# 1_P1.net
KiCad netlist of a schematic drawn in Altium Designer
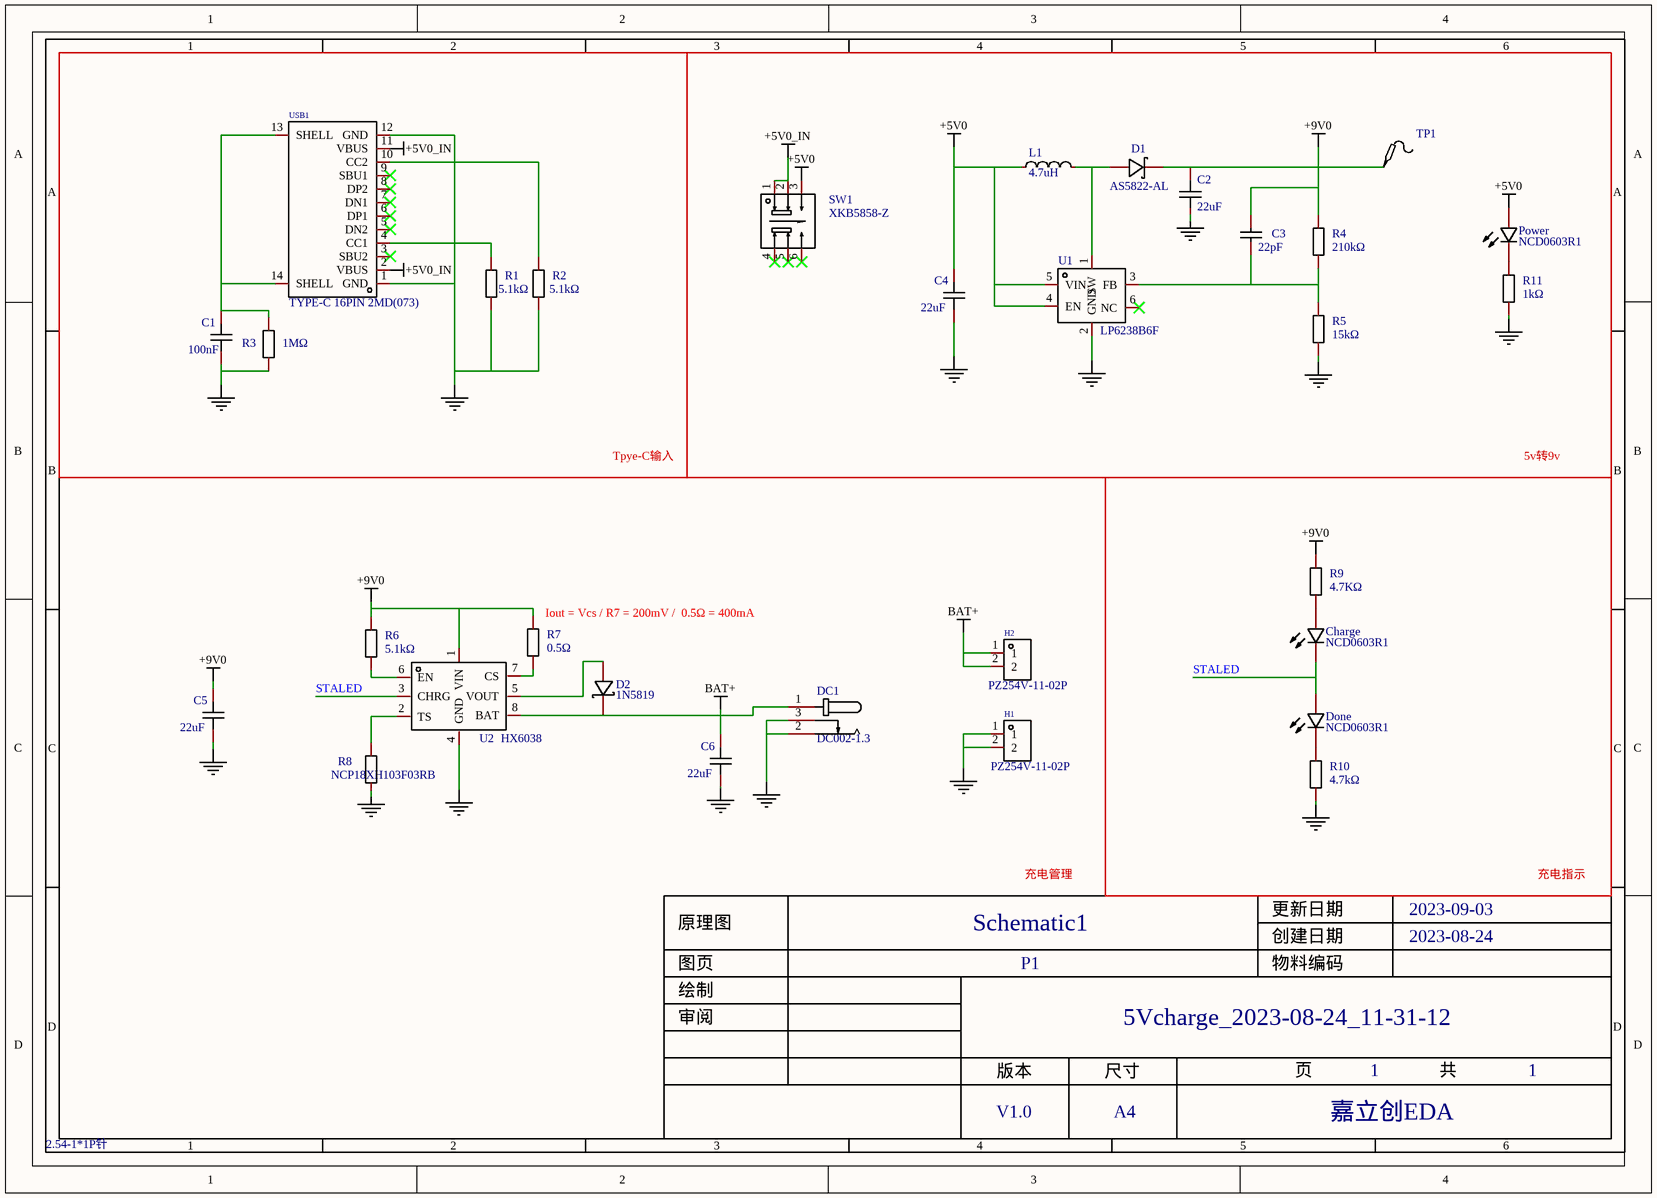
[diagram p0: 1_P1.schdoc]

(export (version "E")
  (design (tool "Eeschema 10.0.6"))
  (components
    (comp (ref "C1")
      (value "100nF")
      (description "容值:100nF;精度:±10%;额定电压:50V;材质(温度系数):X7R;")
      (fields
        (field (name "NAME") "100nF")
        (field (name "MANUFACTURER") "YAGEO(国巨)")
        (field (name "MANUFACTURER PART") "CC0603KRX7R9BB104")
      )
      (libsource (lib "altium-import") (part "root_1_CC0603KRX7R9BB104_"))
    )
    (comp (ref "C2")
      (value "22uF")
      (description "容值:22uF;精度:±10%;额定电压:25V;材质(温度系数):X5R;")
      (fields
        (field (name "NAME") "22uF")
        (field (name "MANUFACTURER") "SAMSUNG(三星)")
        (field (name "MANUFACTURER PART") "CL31A226KAHNNNE")
      )
      (libsource (lib "altium-import") (part "root_1_CL31A226KAHNNNE_"))
    )
    (comp (ref "C3")
      (value "22pF")
      (description "容值:22pF;精度:±5%;额定电压:50V;材质(温度系数):NP0;")
      (fields
        (field (name "NAME") "22pF")
        (field (name "MANUFACTURER") "YAGEO(国巨)")
        (field (name "MANUFACTURER PART") "CC0603JRNPO9BN220")
      )
      (libsource (lib "altium-import") (part "root_1_CC0603JRNPO9BN220_"))
    )
    (comp (ref "C4")
      (value "22uF")
      (description "容值:22uF;精度:±10%;额定电压:25V;材质(温度系数):X5R;")
      (fields
        (field (name "NAME") "22uF")
        (field (name "MANUFACTURER") "SAMSUNG(三星)")
        (field (name "MANUFACTURER PART") "CL31A226KAHNNNE")
      )
      (libsource (lib "altium-import") (part "root_1_CL31A226KAHNNNE_"))
    )
    (comp (ref "C5")
      (value "22uF")
      (description "容值:22uF;精度:±10%;额定电压:25V;材质(温度系数):X5R;")
      (fields
        (field (name "NAME") "22uF")
        (field (name "MANUFACTURER") "SAMSUNG(三星)")
        (field (name "MANUFACTURER PART") "CL31A226KAHNNNE")
      )
      (libsource (lib "altium-import") (part "root_1_CL31A226KAHNNNE_"))
    )
    (comp (ref "C6")
      (value "22uF")
      (description "容值:22uF;精度:±10%;额定电压:25V;材质(温度系数):X5R;")
      (fields
        (field (name "NAME") "22uF")
        (field (name "MANUFACTURER") "SAMSUNG(三星)")
        (field (name "MANUFACTURER PART") "CL31A226KAHNNNE")
      )
      (libsource (lib "altium-import") (part "root_1_CL31A226KAHNNNE_"))
    )
    (comp (ref "Charge")
      (value "NCD0603R1")
      (description "发光颜色:红灯;")
      (fields (field (name "NAME") "NCD0603R1") (field (name "MANUFACTURER") "国星光电"))
      (libsource (lib "altium-import") (part "root_1_NCD0603R1_C84263_"))
    )
    (comp (ref "D1")
      (value "AS5822-AL")
      (description "二极管配置:独立式;直流反向耐压(Vr):40V;平均整流电流(Io):3A;正向压降(Vf):500mV@3A;反向电流(Ir):500uA@40V;")
      (fields (field (name "NAME") "AS5822-AL") (field (name "MANUFACTURER") "AnBon(安邦)"))
      (libsource (lib "altium-import") (part "root_2_AS5822-AL_"))
    )
    (comp (ref "D2")
      (value "1N5819")
      (description "直流反向耐压(Vr):40V;平均整流电流(Io):1A;正向压降(Vf):500mV@1A;")
      (fields (field (name "NAME") "1N5819") (field (name "MANUFACTURER") "KEXIN(科信)"))
      (libsource (lib "altium-import") (part "root_1_1N5819_C437199_"))
    )
    (comp (ref "DC1")
      (value "DC002-1.3")
      (description "连接器类型:DC电源插座;安装方式:弯插;触点内径:2mm;触点外径:6.3mm;额定电流:500mA;额定电压:30V;工作温度范围:-40℃~+55℃;")
      (fields (field (name "NAME") "DC002-1.3") (field (name "MANUFACTURER") "SHOU HAN(首韩)"))
      (libsource (lib "altium-import") (part "root_0_mirrored_DC002-1.3_"))
    )
    (comp (ref "Done")
      (value "NCD0603R1")
      (description "发光颜色:红灯;")
      (fields (field (name "NAME") "NCD0603R1") (field (name "MANUFACTURER") "国星光电"))
      (libsource (lib "altium-import") (part "root_1_NCD0603R1_C84263_"))
    )
    (comp (ref "H1")
      (value "PZ254V-11-02P")
      (fields (field (name "NAME") "PZ254V-11-02P") (field (name "MANUFACTURER") "XFCN(兴飞)"))
      (libsource (lib "altium-import") (part "root_0_PZ254V-11-02P_"))
    )
    (comp (ref "H2")
      (value "PZ254V-11-02P")
      (fields (field (name "NAME") "PZ254V-11-02P") (field (name "MANUFACTURER") "XFCN(兴飞)"))
      (libsource (lib "altium-import") (part "root_0_PZ254V-11-02P_"))
    )
    (comp (ref "L1")
      (value "4.7uH")
      (description "直流电阻(DCR):78mΩ;精度:±20%;电感值:4.7uH;额定电流:2A;")
      (fields
        (field (name "NAME") "4.7uH")
        (field (name "MANUFACTURER") "Sunlord(顺络)")
        (field (name "MANUFACTURER PART") "SWPA4030S4R7MT")
      )
      (libsource (lib "altium-import") (part "root_0_SWPA4030S4R7MT_"))
    )
    (comp (ref "Power")
      (value "NCD0603R1")
      (description "发光颜色:红灯;")
      (fields (field (name "NAME") "NCD0603R1") (field (name "MANUFACTURER") "国星光电"))
      (libsource (lib "altium-import") (part "root_1_NCD0603R1_C84263_"))
    )
    (comp (ref "R1")
      (value "5.1kΩ")
      (description "电阻类型:厚膜电阻;阻值:5.1kΩ;精度:±1%;功率:100mW;")
      (fields
        (field (name "NAME") "5.1kΩ")
        (field (name "MANUFACTURER") "UNI-ROYAL(厚声)")
        (field (name "MANUFACTURER PART") "0603WAF5101T5E")
      )
      (libsource (lib "altium-import") (part "root_3_0603WAF5101T5E_"))
    )
    (comp (ref "R2")
      (value "5.1kΩ")
      (description "电阻类型:厚膜电阻;阻值:5.1kΩ;精度:±1%;功率:100mW;")
      (fields
        (field (name "NAME") "5.1kΩ")
        (field (name "MANUFACTURER") "UNI-ROYAL(厚声)")
        (field (name "MANUFACTURER PART") "0603WAF5101T5E")
      )
      (libsource (lib "altium-import") (part "root_3_0603WAF5101T5E_"))
    )
    (comp (ref "R3")
      (value "1MΩ")
      (description "电阻类型:厚膜电阻;阻值:10kΩ;精度:±1%;功率:100mW;")
      (fields
        (field (name "NAME") "1MΩ")
        (field (name "MANUFACTURER") "UNI-ROYAL(厚声)")
        (field (name "MANUFACTURER PART") "0603WAF1002T5E")
      )
      (libsource (lib "altium-import") (part "root_1_0603WAF1002T5E_"))
    )
    (comp (ref "R4")
      (value "210kΩ")
      (description "电阻类型:厚膜电阻;阻值:210kΩ;精度:±1%;功率:100mW;")
      (fields
        (field (name "NAME") "210kΩ")
        (field (name "MANUFACTURER") "UNI-ROYAL(厚声)")
        (field (name "MANUFACTURER PART") "0603WAF2103T5E")
      )
      (libsource (lib "altium-import") (part "root_1_0603WAF2103T5E_"))
    )
    (comp (ref "R5")
      (value "15kΩ")
      (description "电阻类型:厚膜电阻;阻值:5.1kΩ;精度:±1%;功率:100mW;")
      (fields
        (field (name "NAME") "15kΩ")
        (field (name "MANUFACTURER") "UNI-ROYAL(厚声)")
        (field (name "MANUFACTURER PART") "0603WAF5101T5E")
      )
      (libsource (lib "altium-import") (part "root_3_0603WAF5101T5E_"))
    )
    (comp (ref "R6")
      (value "5.1kΩ")
      (description "电阻类型:厚膜电阻;阻值:5.1kΩ;精度:±1%;功率:100mW;")
      (fields
        (field (name "NAME") "5.1kΩ")
        (field (name "MANUFACTURER") "UNI-ROYAL(厚声)")
        (field (name "MANUFACTURER PART") "0603WAF5101T5E")
      )
      (libsource (lib "altium-import") (part "root_3_0603WAF5101T5E_"))
    )
    (comp (ref "R7")
      (value "0.5Ω")
      (description "电阻类型:厚膜电阻;阻值:5.1kΩ;精度:±1%;功率:100mW;")
      (fields
        (field (name "NAME") "0.5Ω")
        (field (name "MANUFACTURER") "UNI-ROYAL(厚声)")
        (field (name "MANUFACTURER PART") "0603WAF5101T5E")
      )
      (libsource (lib "altium-import") (part "root_3_0603WAF5101T5E_"))
    )
    (comp (ref "R8")
      (value "NCP18XH103F03RB")
      (fields
        (field (name "NAME") "NCP18XH103F03RB")
        (field (name "MANUFACTURER") "muRata(村田)")
        (field (name "POWER") "100mW")
        (field (name "TOLERANCE") "±1%")
      )
      (libsource (lib "altium-import") (part "root_3_NCP18XH103F03RB_"))
    )
    (comp (ref "R9")
      (value "4.7KΩ")
      (description "电阻类型:厚膜电阻;阻值:5.1kΩ;精度:±1%;功率:100mW;")
      (fields
        (field (name "NAME") "4.7KΩ")
        (field (name "MANUFACTURER") "UNI-ROYAL(厚声)")
        (field (name "MANUFACTURER PART") "0603WAF5101T5E")
      )
      (libsource (lib "altium-import") (part "root_3_0603WAF5101T5E_"))
    )
    (comp (ref "R10")
      (value "4.7kΩ")
      (description "电阻类型:厚膜电阻;阻值:5.1kΩ;精度:±1%;功率:100mW;")
      (fields
        (field (name "NAME") "4.7kΩ")
        (field (name "MANUFACTURER") "UNI-ROYAL(厚声)")
        (field (name "MANUFACTURER PART") "0603WAF5101T5E")
      )
      (libsource (lib "altium-import") (part "root_3_0603WAF5101T5E_"))
    )
    (comp (ref "R11")
      (value "1kΩ")
      (description "电阻类型:厚膜电阻;阻值:5.1kΩ;精度:±1%;功率:100mW;")
      (fields
        (field (name "NAME") "1kΩ")
        (field (name "MANUFACTURER") "UNI-ROYAL(厚声)")
        (field (name "MANUFACTURER PART") "0603WAF5101T5E")
      )
      (libsource (lib "altium-import") (part "root_3_0603WAF5101T5E_"))
    )
    (comp (ref "SW1")
      (value "XKB5858-Z")
      (fields (field (name "NAME") "XKB5858-Z") (field (name "MANUFACTURER") "XKB Connectivity(中国星坤)"))
      (libsource (lib "altium-import") (part "root_2_XKB5858-Z_"))
    )
    (comp (ref "TP1")
      (value "2.54-1*1P针")
      (description "排数:单排;总PIN位数:1P;间距:-;插针结构:-;行距:-;安装类型:直插;圆针/方针:-;额定电流:-;额定电压:-;配合针长度:-;塑高:-;触头材质:-;触头镀层:-;颜色:黑色;")
      (fields (field (name "NAME") "2.54-1*1P针") (field (name "MANUFACTURER") "BOOMELE(博穆精密)"))
      (libsource (lib "altium-import") (part "root_0_2.54-1*1P针_"))
    )
    (comp (ref "U1")
      (value "LP6238B6F")
      (description "2.6A MOS电流")
      (fields (field (name "NAME") "LP6238B6F") (field (name "MANUFACTURER") "LOWPOWER(微源半导体)"))
      (libsource (lib "altium-import") (part "root_0_LP6238B6F_"))
    )
    (comp (ref "U2")
      (value "HX6038")
      (fields (field (name "NAME") "HX6038") (field (name "MANUFACTURER") "INJOINIC(英集芯)"))
      (libsource (lib "altium-import") (part "root_0_IP2312U_"))
    )
    (comp (ref "USB1")
      (value "TYPE-C 16PIN 2MD(073)")
      (description "连接器类型:Type-C;标准:-;公母:母座;触点数量:16;端口数量:1;安装方式:卧贴;额定电流 - 电源:5A;工作温度范围:-25℃~+85℃;")
      (fields (field (name "NAME") "TYPE-C 16PIN 2MD(073)") (field (name "MANUFACTURER") "SHOU HAN(首韩)"))
      (libsource (lib "altium-import") (part "root_2_TYPE-C 16PIN 2MD(073)_"))
    )
  )
  (nets
    (net (code "1") (name "+5V0") (class "Default")
      (node (ref "C4") (pin "2") (pinfunction "2_2") (pintype "passive"))
      (node (ref "L1") (pin "1") (pinfunction "1_1") (pintype "passive"))
      (node (ref "Power") (pin "2") (pinfunction "A_2") (pintype "passive"))
      (node (ref "SW1") (pin "3") (pinfunction "3_3") (pintype "passive"))
      (node (ref "U1") (pin "4") (pinfunction "EN_4") (pintype "passive"))
      (node (ref "U1") (pin "5") (pinfunction "VIN_5") (pintype "passive"))
    )
    (net (code "2") (name "+5V0_IN") (class "Default")
      (node (ref "SW1") (pin "1") (pinfunction "1_1") (pintype "passive"))
      (node (ref "SW1") (pin "2") (pinfunction "2_2") (pintype "passive"))
      (node (ref "USB1") (pin "11") (pinfunction "VBUS_11") (pintype "passive"))
      (node (ref "USB1") (pin "2") (pinfunction "VBUS_2") (pintype "passive"))
    )
    (net (code "3") (name "+9V0") (class "Default")
      (node (ref "C2") (pin "2") (pinfunction "2_2") (pintype "passive"))
      (node (ref "C3") (pin "2") (pinfunction "2_2") (pintype "passive"))
      (node (ref "C5") (pin "2") (pinfunction "2_2") (pintype "passive"))
      (node (ref "D1") (pin "1") (pinfunction "A_1") (pintype "passive"))
      (node (ref "R4") (pin "2") (pinfunction "2_2") (pintype "passive"))
      (node (ref "R6") (pin "1") (pinfunction "1_1") (pintype "passive"))
      (node (ref "R7") (pin "1") (pinfunction "1_1") (pintype "passive"))
      (node (ref "R9") (pin "1") (pinfunction "1_1") (pintype "passive"))
      (node (ref "TP1") (pin "1") (pinfunction "1_1") (pintype "passive"))
      (node (ref "U2") (pin "1") (pinfunction "VIN_1") (pintype "passive"))
    )
    (net (code "4") (name "/STALED") (class "Default")
      (node (ref "Charge") (pin "1") (pinfunction "K_1") (pintype "passive"))
      (node (ref "Done") (pin "2") (pinfunction "A_2") (pintype "passive"))
      (node (ref "U2") (pin "3") (pinfunction "CHRG_3") (pintype "passive"))
    )
    (net (code "5") (name "<NO NET>") (class "Default")
      (node (ref "C1") (pin "1") (pinfunction "1_1") (pintype "passive"))
      (node (ref "C2") (pin "1") (pinfunction "1_1") (pintype "passive"))
      (node (ref "C4") (pin "1") (pinfunction "1_1") (pintype "passive"))
      (node (ref "C5") (pin "1") (pinfunction "1_1") (pintype "passive"))
      (node (ref "C6") (pin "1") (pinfunction "1_1") (pintype "passive"))
      (node (ref "DC1") (pin "2") (pinfunction "2_2") (pintype "passive"))
      (node (ref "DC1") (pin "3") (pinfunction "3_3") (pintype "passive"))
      (node (ref "H1") (pin "1") (pinfunction "1_1") (pintype "passive"))
      (node (ref "H1") (pin "2") (pinfunction "2_2") (pintype "passive"))
      (node (ref "R1") (pin "2") (pinfunction "2_2") (pintype "passive"))
      (node (ref "R10") (pin "2") (pinfunction "2_2") (pintype "passive"))
      (node (ref "R11") (pin "2") (pinfunction "2_2") (pintype "passive"))
      (node (ref "R2") (pin "2") (pinfunction "2_2") (pintype "passive"))
      (node (ref "R3") (pin "1") (pinfunction "1_1") (pintype "passive"))
      (node (ref "R5") (pin "2") (pinfunction "2_2") (pintype "passive"))
      (node (ref "R8") (pin "2") (pinfunction "2_2") (pintype "passive"))
      (node (ref "U1") (pin "2") (pinfunction "GND_2") (pintype "passive"))
      (node (ref "U2") (pin "4") (pinfunction "GND_4") (pintype "passive"))
      (node (ref "USB1") (pin "1") (pinfunction "GND_1") (pintype "passive"))
      (node (ref "USB1") (pin "12") (pinfunction "GND_12") (pintype "passive"))
    )
    (net (code "6") (name "BAT+") (class "Default")
      (node (ref "C6") (pin "2") (pinfunction "2_2") (pintype "passive"))
      (node (ref "D2") (pin "1") (pinfunction "C_1") (pintype "passive"))
      (node (ref "DC1") (pin "1") (pinfunction "1_1") (pintype "passive"))
      (node (ref "H2") (pin "1") (pinfunction "1_1") (pintype "passive"))
      (node (ref "H2") (pin "2") (pinfunction "2_2") (pintype "passive"))
      (node (ref "U2") (pin "8") (pinfunction "BAT_8") (pintype "passive"))
    )
    (net (code "7") (name "Net-(C1-Pad2)") (class "Default")
      (node (ref "C1") (pin "2") (pinfunction "2_2") (pintype "passive"))
      (node (ref "R3") (pin "2") (pinfunction "2_2") (pintype "passive"))
      (node (ref "USB1") (pin "13") (pinfunction "SHELL_13") (pintype "passive"))
      (node (ref "USB1") (pin "14") (pinfunction "SHELL_14") (pintype "passive"))
    )
    (net (code "8") (name "Net-(Charge-A)") (class "Default")
      (node (ref "Charge") (pin "2") (pinfunction "A_2") (pintype "passive"))
      (node (ref "R9") (pin "2") (pinfunction "2_2") (pintype "passive"))
    )
    (net (code "9") (name "Net-(D1-K)") (class "Default")
      (node (ref "D1") (pin "2") (pinfunction "K_2") (pintype "passive"))
      (node (ref "L1") (pin "2") (pinfunction "2_2") (pintype "passive"))
      (node (ref "U1") (pin "1") (pinfunction "SW_1") (pintype "passive"))
    )
    (net (code "10") (name "Net-(D2-A)") (class "Default")
      (node (ref "D2") (pin "2") (pinfunction "A_2") (pintype "passive"))
      (node (ref "U2") (pin "5") (pinfunction "VOUT_5") (pintype "passive"))
    )
    (net (code "11") (name "Net-(Done-K)") (class "Default")
      (node (ref "Done") (pin "1") (pinfunction "K_1") (pintype "passive"))
      (node (ref "R10") (pin "1") (pinfunction "1_1") (pintype "passive"))
    )
    (net (code "12") (name "Net-(Power-K)") (class "Default")
      (node (ref "Power") (pin "1") (pinfunction "K_1") (pintype "passive"))
      (node (ref "R11") (pin "1") (pinfunction "1_1") (pintype "passive"))
    )
    (net (code "13") (name "Net-(U1-FB)") (class "Default")
      (node (ref "C3") (pin "1") (pinfunction "1_1") (pintype "passive"))
      (node (ref "R4") (pin "1") (pinfunction "1_1") (pintype "passive"))
      (node (ref "R5") (pin "1") (pinfunction "1_1") (pintype "passive"))
      (node (ref "U1") (pin "3") (pinfunction "FB_3") (pintype "passive"))
    )
    (net (code "14") (name "Net-(U2-CS)") (class "Default")
      (node (ref "R7") (pin "2") (pinfunction "2_2") (pintype "passive"))
      (node (ref "U2") (pin "7") (pinfunction "CS_7") (pintype "passive"))
    )
    (net (code "15") (name "Net-(U2-EN)") (class "Default")
      (node (ref "R6") (pin "2") (pinfunction "2_2") (pintype "passive"))
      (node (ref "U2") (pin "6") (pinfunction "EN_6") (pintype "passive"))
    )
    (net (code "16") (name "Net-(U2-TS)") (class "Default")
      (node (ref "R8") (pin "1") (pinfunction "1_1") (pintype "passive"))
      (node (ref "U2") (pin "2") (pinfunction "TS_2") (pintype "passive"))
    )
    (net (code "17") (name "Net-(USB1-CC1)") (class "Default")
      (node (ref "R1") (pin "1") (pinfunction "1_1") (pintype "passive"))
      (node (ref "USB1") (pin "4") (pinfunction "CC1_4") (pintype "passive"))
    )
    (net (code "18") (name "Net-(USB1-CC2)") (class "Default")
      (node (ref "R2") (pin "1") (pinfunction "1_1") (pintype "passive"))
      (node (ref "USB1") (pin "10") (pinfunction "CC2_10") (pintype "passive"))
    )
    (net (code "19") (name "unconnected-(SW1-Pad4)") (class "Default")
      (node (ref "SW1") (pin "4") (pinfunction "4_4") (pintype "passive+no_connect"))
    )
    (net (code "20") (name "unconnected-(SW1-Pad5)") (class "Default")
      (node (ref "SW1") (pin "5") (pinfunction "5_5") (pintype "passive+no_connect"))
    )
    (net (code "21") (name "unconnected-(SW1-Pad6)") (class "Default")
      (node (ref "SW1") (pin "6") (pinfunction "6_6") (pintype "passive+no_connect"))
    )
    (net (code "22") (name "unconnected-(U1-NC-Pad6)") (class "Default")
      (node (ref "U1") (pin "6") (pinfunction "NC_6") (pintype "passive+no_connect"))
    )
    (net (code "23") (name "unconnected-(USB1-DN1-Pad7)") (class "Default")
      (node (ref "USB1") (pin "7") (pinfunction "DN1_7") (pintype "passive+no_connect"))
    )
    (net (code "24") (name "unconnected-(USB1-DN2-Pad5)") (class "Default")
      (node (ref "USB1") (pin "5") (pinfunction "DN2_5") (pintype "passive+no_connect"))
    )
    (net (code "25") (name "unconnected-(USB1-DP1-Pad6)") (class "Default")
      (node (ref "USB1") (pin "6") (pinfunction "DP1_6") (pintype "passive+no_connect"))
    )
    (net (code "26") (name "unconnected-(USB1-DP2-Pad8)") (class "Default")
      (node (ref "USB1") (pin "8") (pinfunction "DP2_8") (pintype "passive+no_connect"))
    )
    (net (code "27") (name "unconnected-(USB1-SBU1-Pad9)") (class "Default")
      (node (ref "USB1") (pin "9") (pinfunction "SBU1_9") (pintype "passive+no_connect"))
    )
    (net (code "28") (name "unconnected-(USB1-SBU2-Pad3)") (class "Default")
      (node (ref "USB1") (pin "3") (pinfunction "SBU2_3") (pintype "passive+no_connect"))
    )
  )
)
